# LM2596.net
KiCad netlist of a schematic drawn in Altium Designer
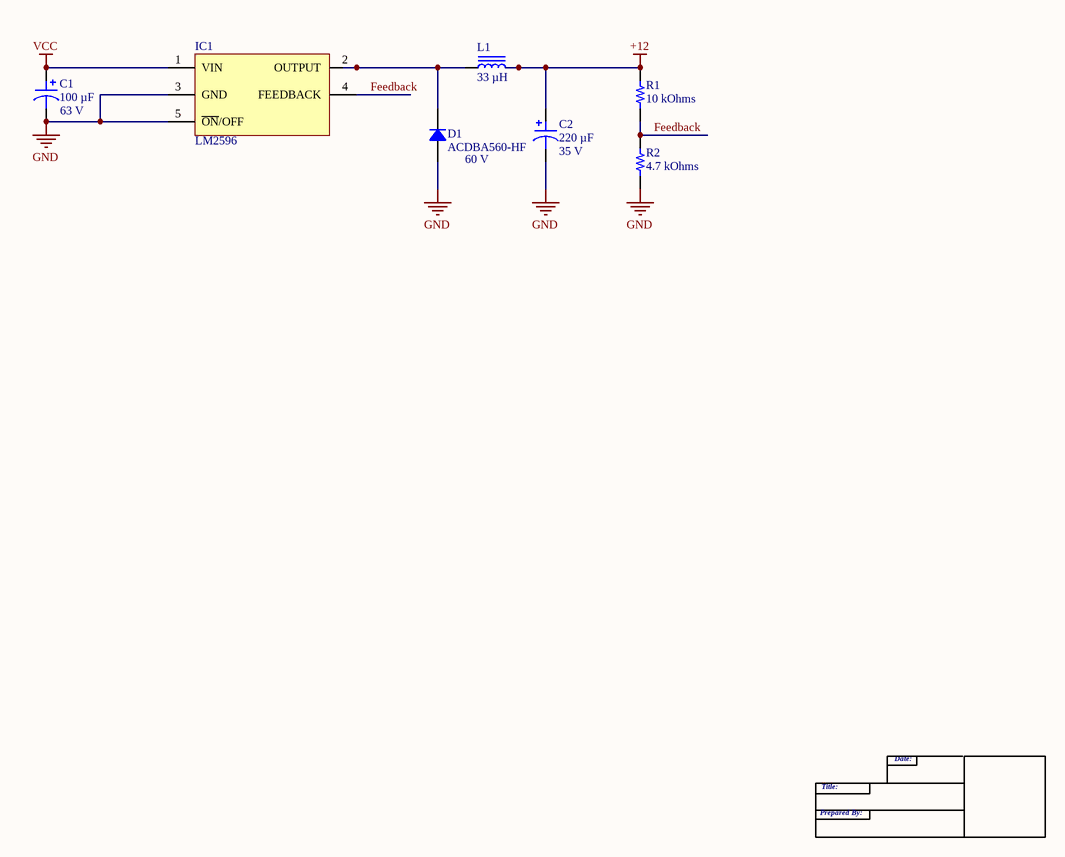
[diagram p0: LM2596.SchDoc]

(export (version "E")
  (design (tool "Eeschema 10.0.6"))
  (components
    (comp (ref "C1")
      (value "100 µF")
      (footprint "CAP AL TH D8 L3.5 H12.5")
      (description "CAP ALUM 100UF 20% 63V RADIAL")
      (fields
        (field (name "PART NUMBER") "ECA-1JM101")
        (field (name "MANUFACTURER") "Panasonic Electronic Components")
        (field (name "VOLTAGE - RATED") "63 V")
      )
      (libsource (lib "") (part "Polarised Capacitor_1"))
    )
    (comp (ref "C2")
      (value "220 µF")
      (footprint "CAP AL TH D8 L3.5 H12.5")
      (description "CAP ALUM 220UF 20% 35V RADIAL")
      (fields
        (field (name "PART NUMBER") "ECA-1VM221")
        (field (name "MANUFACTURER") "Panasonic Electronic Components")
        (field (name "VOLTAGE - RATED") "35 V")
      )
      (libsource (lib "Celestial Altium Library - altium_library") (part "Polarised Capacitor"))
    )
    (comp (ref "D1")
      (value "ACDBA560-HF")
      (footprint "DO214AC SMA")
      (description "DIODE SCHOTTKY 60V 5A DO214AC")
      (fields
        (field (name "MANUFACTURER") "Comchip Technology")
        (field (name "VOLTAGE - DC REVERSE (VR) (MAX)") "60 V")
      )
      (libsource (lib "Celestial Altium Library - altium_library") (part "Diode"))
    )
    (comp (ref "IC1") (value "LM2596") (footprint "PcbLib1:D2PAK") (libsource (lib "Altium") (part "LM2596")))
    (comp (ref "L1")
      (value "33 µH")
      (footprint "BOURNS SRR1280")
      (description "FIXED IND 33UH 3.5A 57 MOHM SMD")
      (fields (field (name "PART NUMBER") "SRR1280-330M") (field (name "MANUFACTURER") "Bourns Inc."))
      (libsource (lib "Celestial Altium Library - altium_library") (part "Inductor"))
    )
    (comp (ref "R1")
      (value "10 kOhms")
      (footprint "RES 0805_2012")
      (description "RES 10K OHM 1% 1/4W 0805")
      (fields
        (field (name "PART NUMBER") "RNCP0805FTD10K0")
        (field (name "MANUFACTURER") "Stackpole Electronics Inc")
      )
      (libsource (lib "Celestial Altium Library - altium_library") (part "Resistor"))
    )
    (comp (ref "R2")
      (value "4.7 kOhms")
      (footprint "RES 0805_2012")
      (description "RES 4.7K OHM 1% 1/3W 0805")
      (fields
        (field (name "PART NUMBER") "CRGP0805F4K7")
        (field (name "MANUFACTURER") "TE Connectivity Passive Product")
      )
      (libsource (lib "Celestial Altium Library - altium_library") (part "Resistor"))
    )
  )
  (nets
    (net (code "1") (name "+12") (class "Default")
      (node (ref "C2") (pin "1") (pinfunction "1_1") (pintype "passive"))
      (node (ref "L1") (pin "2") (pinfunction "2_2") (pintype "passive"))
      (node (ref "R1") (pin "2") (pinfunction "2_2") (pintype "passive"))
    )
    (net (code "2") (name "/Feedback") (class "Default")
      (node (ref "IC1") (pin "4") (pinfunction "FEEDBACK_4") (pintype "passive"))
      (node (ref "R1") (pin "1") (pinfunction "1_1") (pintype "passive"))
      (node (ref "R2") (pin "2") (pinfunction "2_2") (pintype "passive"))
    )
    (net (code "3") (name "GND") (class "Default")
      (node (ref "C1") (pin "2") (pinfunction "2_2") (pintype "passive"))
      (node (ref "C2") (pin "2") (pinfunction "2_2") (pintype "passive"))
      (node (ref "D1") (pin "1") (pinfunction "1_1") (pintype "passive"))
      (node (ref "IC1") (pin "3") (pinfunction "GND_3") (pintype "passive"))
      (node (ref "IC1") (pin "5") (pinfunction "~{ON}/OFF_5") (pintype "passive"))
      (node (ref "R2") (pin "1") (pinfunction "1_1") (pintype "passive"))
    )
    (net (code "4") (name "Net-(IC1-OUTPUT)") (class "Default")
      (node (ref "D1") (pin "2") (pinfunction "2_2") (pintype "passive"))
      (node (ref "IC1") (pin "2") (pinfunction "OUTPUT_2") (pintype "passive"))
      (node (ref "L1") (pin "1") (pinfunction "1_1") (pintype "passive"))
    )
    (net (code "5") (name "VCC") (class "Default")
      (node (ref "C1") (pin "1") (pinfunction "1_1") (pintype "passive"))
      (node (ref "IC1") (pin "1") (pinfunction "VIN_1") (pintype "passive"))
    )
  )
)
